# Power_Tree.net
KiCad netlist of a schematic drawn in Altium Designer
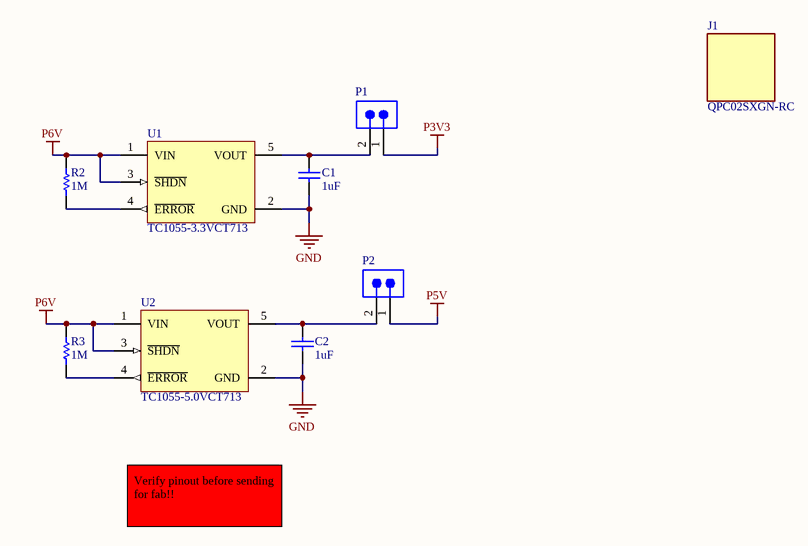
[diagram p0: Power_Tree.SchDoc]

(export (version "E")
  (design (tool "Eeschema 10.0.6"))
  (components
    (comp (ref "C1")
      (value "1uF")
      (footprint "FOOTPRINT-1206-GEN")
      (description "CAP CER 1UF 50V X7R 1206 ±10% 50V Ceramic Capacitor X7R 1206 (3216 Metric)")
      (fields
        (field (name "PART NUMBER") "1276-6781-1-ND")
        (field (name "Comment") "1206 1uF")
        (field (name "PUBLISHER") "Altium Limited")
      )
      (libsource (lib "University of California Riverside - FSAE") (part "Symbol"))
    )
    (comp (ref "C2")
      (value "1uF")
      (footprint "FOOTPRINT-1206-GEN")
      (description "CAP CER 1UF 50V X7R 1206 ±10% 50V Ceramic Capacitor X7R 1206 (3216 Metric)")
      (fields
        (field (name "PART NUMBER") "1276-6781-1-ND")
        (field (name "Comment") "1206 1uF")
        (field (name "PUBLISHER") "Altium Limited")
      )
      (libsource (lib "University of California Riverside - FSAE") (part "Symbol"))
    )
    (comp (ref "J1")
      (value "QPC02SXGN-RC")
      (footprint "FP-QPC02SXGN-RC-MFG")
      (description "CONN JUMPER SHORTING .100\" GOLD")
      (fields
        (field (name "MANUFACTURER") "Sullins")
        (field (name "OCTOPART") "https://octopart.com/qpc02sxgn-rc-sullins-19878795")
      )
      (libsource (lib "Altium Content Vault") (part "87292ac8601c6cf2061292f5bede09e"))
    )
    (comp (ref "P1")
      (value "TSW-102-26-F-S")
      (footprint "SMTC-TSW-102-26-XX-S")
      (description "Headers & Wire Housings Classic PCB Header Strips, 0.100 pitch")
      (libsource (lib "University of California Riverside - FSAE") (part "SMTC-TSW-102-X-X-S-X"))
    )
    (comp (ref "P2")
      (value "TSW-102-26-F-S")
      (footprint "SMTC-TSW-102-26-XX-S")
      (description "Headers & Wire Housings Classic PCB Header Strips, 0.100 pitch")
      (libsource (lib "University of California Riverside - FSAE") (part "SMTC-TSW-102-X-X-S-X"))
    )
    (comp (ref "R2")
      (value "1M")
      (footprint "RESC3116X65X50NL20T20")
      (description "CRCW12061M00FKEAHP\r\n1M 1206")
      (fields (field (name "MANUFACTURER") "Vishay Dale") (field (name "PART NUMBER") "CRCW12061M00FKEAHP"))
      (libsource (lib "Altium Content Vault") (part "RES"))
    )
    (comp (ref "R3")
      (value "1M")
      (footprint "RESC3116X65X50NL20T20")
      (description "CRCW12061M00FKEAHP\r\n1M 1206")
      (fields (field (name "MANUFACTURER") "Vishay Dale") (field (name "PART NUMBER") "CRCW12061M00FKEAHP"))
      (libsource (lib "Altium Content Vault") (part "RES"))
    )
    (comp (ref "U1")
      (value "TC1055-3.3VCT713")
      (footprint "SOT-23-CT5_L")
      (libsource (lib "Altium Content Vault") (part "PM-LINEREG-TC1054-IL5"))
    )
    (comp (ref "U2")
      (value "TC1055-5.0VCT713")
      (footprint "SOT-23-CT5_N")
      (libsource (lib "Altium Content Vault") (part "PM-LINEREG-TC1054-IL5"))
    )
  )
  (nets
    (net (code "1") (name "GND") (class "Default")
      (node (ref "C1") (pin "1") (pinfunction "1_1") (pintype "passive"))
      (node (ref "C2") (pin "1") (pinfunction "1_1") (pintype "passive"))
      (node (ref "U1") (pin "2") (pinfunction "GND_2") (pintype "power_in"))
      (node (ref "U2") (pin "2") (pinfunction "GND_2") (pintype "power_in"))
    )
    (net (code "2") (name "Net-(U1-VOUT)") (class "Default")
      (node (ref "C1") (pin "2") (pinfunction "2_2") (pintype "passive"))
      (node (ref "P1") (pin "2") (pinfunction "2_2") (pintype "passive"))
      (node (ref "U1") (pin "5") (pinfunction "VOUT_5") (pintype "power_in"))
    )
    (net (code "3") (name "Net-(U1-~{ERROR})") (class "Default")
      (node (ref "R2") (pin "1") (pinfunction "1_1") (pintype "passive"))
      (node (ref "U1") (pin "4") (pinfunction "~{ERROR}_4") (pintype "output"))
    )
    (net (code "4") (name "Net-(U2-VOUT)") (class "Default")
      (node (ref "C2") (pin "2") (pinfunction "2_2") (pintype "passive"))
      (node (ref "P2") (pin "2") (pinfunction "2_2") (pintype "passive"))
      (node (ref "U2") (pin "5") (pinfunction "VOUT_5") (pintype "power_in"))
    )
    (net (code "5") (name "Net-(U2-~{ERROR})") (class "Default")
      (node (ref "R3") (pin "1") (pinfunction "1_1") (pintype "passive"))
      (node (ref "U2") (pin "4") (pinfunction "~{ERROR}_4") (pintype "output"))
    )
    (net (code "6") (name "P3V3") (class "Default")
      (node (ref "P1") (pin "1") (pinfunction "1_1") (pintype "passive"))
    )
    (net (code "7") (name "P5V") (class "Default")
      (node (ref "P2") (pin "1") (pinfunction "1_1") (pintype "passive"))
    )
    (net (code "8") (name "P6V") (class "Default")
      (node (ref "R2") (pin "2") (pinfunction "2_2") (pintype "passive"))
      (node (ref "R3") (pin "2") (pinfunction "2_2") (pintype "passive"))
      (node (ref "U1") (pin "1") (pinfunction "VIN_1") (pintype "power_in"))
      (node (ref "U1") (pin "3") (pinfunction "~{SHDN}_3") (pintype "input"))
      (node (ref "U2") (pin "1") (pinfunction "VIN_1") (pintype "power_in"))
      (node (ref "U2") (pin "3") (pinfunction "~{SHDN}_3") (pintype "input"))
    )
  )
)
